# SCH_NightLightAnnunciator_2021-09-26.net
KiCad netlist of a schematic drawn in EasyEDA
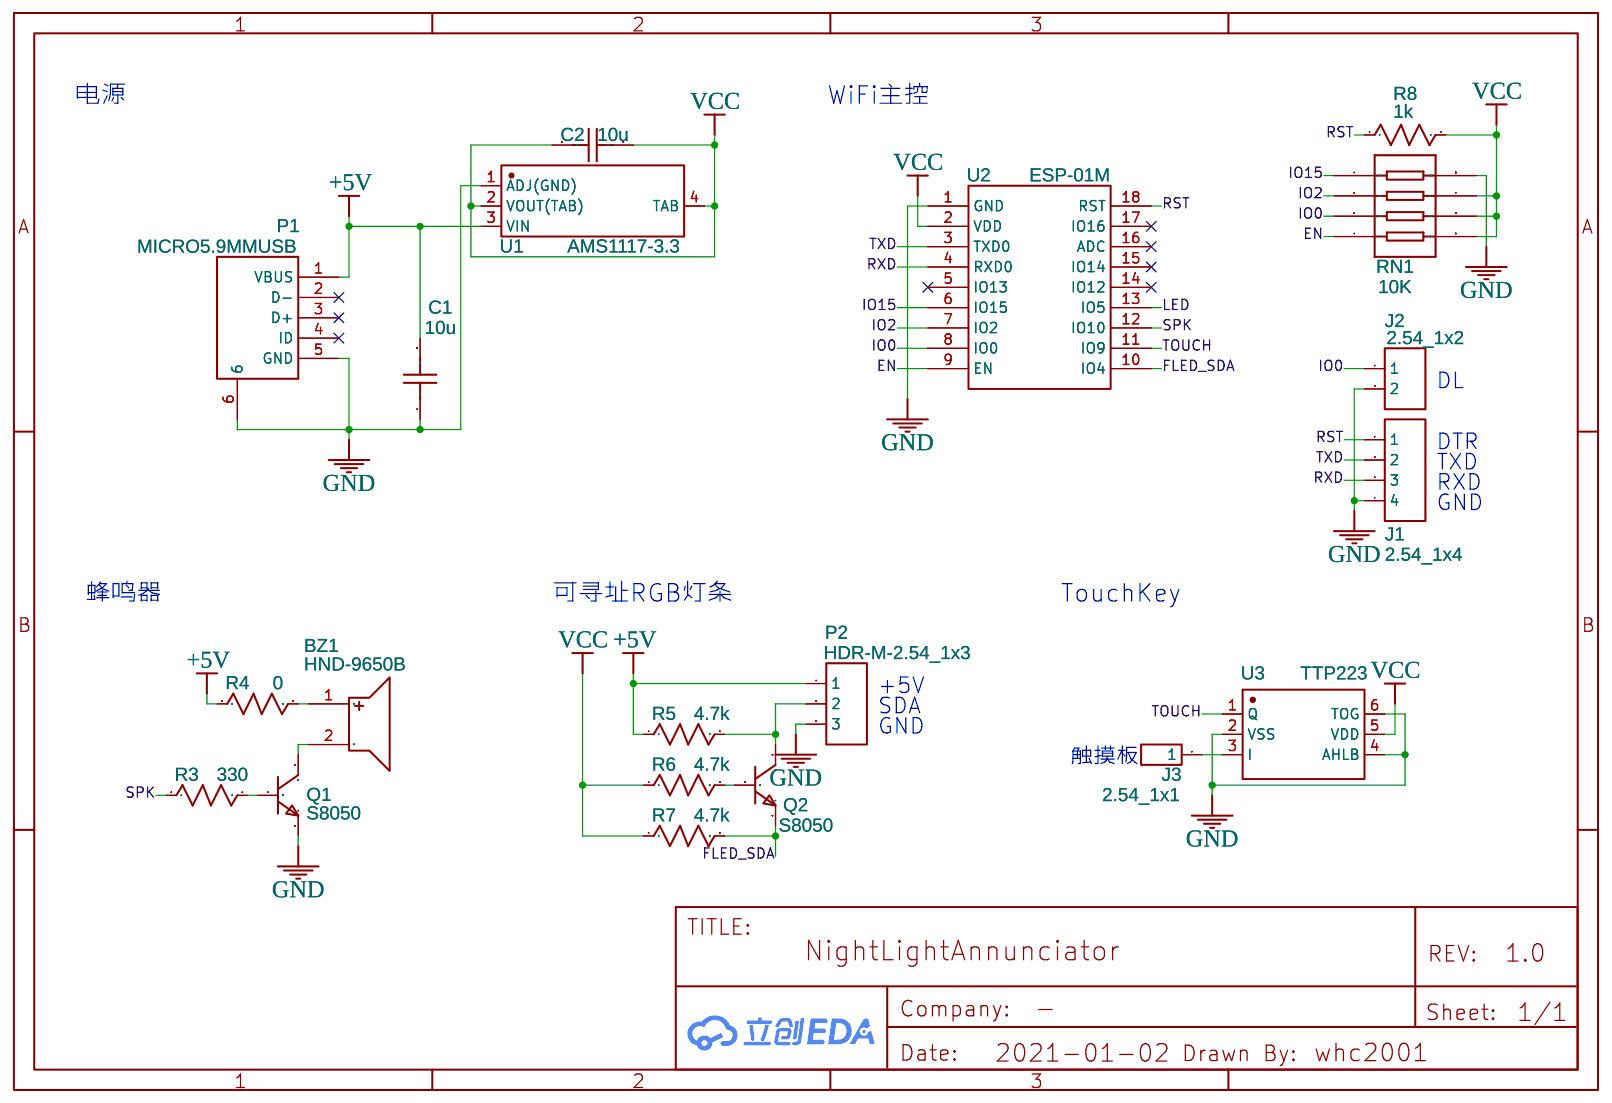
[diagram p0: schematic sheet]

(export (version "E")
  (design (tool "Eeschema 10.0.6"))
  (components
    (comp (ref "BZ1")
      (value "HND-9650B")
      (fields (field (name "BOM_Supplier Part") "C96127"))
      (libsource (lib "") (part "HND-9650B"))
    )
    (comp (ref "C1") (value "10u") (libsource (lib "") (part "C_0603_US")))
    (comp (ref "C2") (value "10u") (libsource (lib "") (part "C_0603_US_1")))
    (comp (ref "J1")
      (value "2.54_1x4")
      (fields (field (name "BOM_Supplier Part") "C124378"))
      (libsource (lib "") (part "HDR-M-2.54_1x4"))
    )
    (comp (ref "J2")
      (value "2.54_1x2")
      (fields (field (name "BOM_Supplier Part") "C124375"))
      (libsource (lib "") (part "HDR-M-2.54_1x2"))
    )
    (comp (ref "J3")
      (value "2.54_1x1")
      (fields (field (name "BOM_Supplier Part") "C81276"))
      (libsource (lib "") (part "HDR-M-2.54_1x1"))
    )
    (comp (ref "P1")
      (value "MICRO5.9MMUSB")
      (fields
        (field (name "BOM_Manufacturer Part") "MICRO5.9mmusb")
        (field (name "BOM_Supplier Part") "C393940")
      )
      (libsource (lib "") (part "MICRO5.9MMUSB"))
    )
    (comp (ref "P2")
      (value "HDR-M-2.54_1x3")
      (fields (field (name "BOM_Supplier Part") "C180248"))
      (libsource (lib "") (part "HDR-M-2.54_1x3"))
    )
    (comp (ref "Q1")
      (value "S8050")
      (fields (field (name "BOM_Manufacturer Part") "S8050-J3Y") (field (name "BOM_Supplier Part") "C364312"))
      (libsource (lib "") (part "S8050-J3Y"))
    )
    (comp (ref "Q2")
      (value "S8050")
      (fields (field (name "BOM_Manufacturer Part") "S8050-J3Y") (field (name "BOM_Supplier Part") "C364312"))
      (libsource (lib "") (part "S8050-J3Y"))
    )
    (comp (ref "R3") (value "330") (libsource (lib "") (part "R_0603_US")))
    (comp (ref "R4") (value "0") (libsource (lib "") (part "R_0603_US")))
    (comp (ref "R5") (value "4.7k") (libsource (lib "") (part "R_0603_US")))
    (comp (ref "R6") (value "4.7k") (libsource (lib "") (part "R_0603_US")))
    (comp (ref "R7") (value "4.7k") (libsource (lib "") (part "R_0603_US")))
    (comp (ref "R8") (value "1k") (libsource (lib "") (part "R_0603_US")))
    (comp (ref "RN1")
      (value "10K")
      (fields
        (field (name "BOM_Manufacturer Part") "CN1J4TTD103J")
        (field (name "BOM_Supplier Part") "C240723")
      )
      (libsource (lib "") (part "CN1J4TTD103J"))
    )
    (comp (ref "U1")
      (value "AMS1117-3.3")
      (fields (field (name "BOM_Supplier Part") "C347222"))
      (libsource (lib "") (part "AMS1117-3.3_C347222"))
    )
    (comp (ref "U2") (value "ESP-01M") (libsource (lib "") (part "ESP-01M")))
    (comp (ref "U3")
      (value "TTP223")
      (fields
        (field (name "BOM_Manufacturer Part") "TTP223E-HA6")
        (field (name "BOM_Supplier Part") "C129459")
      )
      (libsource (lib "") (part "TTP223E-HA6"))
    )
  )
  (nets
    (net (code "1") (name "+5V") (class "Default")
      (node (ref "C1") (pin "2") (pinfunction "2_2") (pintype "unspecified"))
      (node (ref "P1") (pin "1") (pinfunction "VBUS_1") (pintype "unspecified"))
      (node (ref "P2") (pin "1") (pinfunction "1_1") (pintype "input"))
      (node (ref "R4") (pin "1") (pinfunction "1_1") (pintype "unspecified"))
      (node (ref "R5") (pin "1") (pinfunction "1_1") (pintype "unspecified"))
      (node (ref "U1") (pin "3") (pinfunction "VIN_3") (pintype "unspecified"))
    )
    (net (code "2") (name "/EN") (class "Default")
      (node (ref "RN1") (pin "4") (pinfunction "4_4") (pintype "input"))
      (node (ref "U2") (pin "9") (pinfunction "EN_9") (pintype "unspecified"))
    )
    (net (code "3") (name "/FLED_SDA") (class "Default")
      (node (ref "Q2") (pin "2") (pinfunction "E_2") (pintype "unspecified"))
      (node (ref "R7") (pin "2") (pinfunction "2_2") (pintype "unspecified"))
      (node (ref "U2") (pin "10") (pinfunction "IO4_10") (pintype "unspecified"))
    )
    (net (code "4") (name "/IO0") (class "Default")
      (node (ref "J2") (pin "1") (pinfunction "1_1") (pintype "unspecified"))
      (node (ref "RN1") (pin "3") (pinfunction "3_3") (pintype "input"))
      (node (ref "U2") (pin "8") (pinfunction "IO0_8") (pintype "unspecified"))
    )
    (net (code "5") (name "/IO2") (class "Default")
      (node (ref "RN1") (pin "2") (pinfunction "2_2") (pintype "input"))
      (node (ref "U2") (pin "7") (pinfunction "IO2_7") (pintype "unspecified"))
    )
    (net (code "6") (name "/IO15") (class "Default")
      (node (ref "RN1") (pin "1") (pinfunction "1_1") (pintype "input"))
      (node (ref "U2") (pin "6") (pinfunction "IO15_6") (pintype "unspecified"))
    )
    (net (code "7") (name "/LED") (class "Default")
      (node (ref "U2") (pin "13") (pinfunction "IO5_13") (pintype "unspecified"))
    )
    (net (code "8") (name "/RST") (class "Default")
      (node (ref "J1") (pin "1") (pinfunction "1_1") (pintype "unspecified"))
      (node (ref "R8") (pin "1") (pinfunction "1_1") (pintype "unspecified"))
      (node (ref "U2") (pin "18") (pinfunction "RST_18") (pintype "unspecified"))
    )
    (net (code "9") (name "/RXD") (class "Default")
      (node (ref "J1") (pin "3") (pinfunction "3_3") (pintype "unspecified"))
      (node (ref "U2") (pin "4") (pinfunction "RXD0_4") (pintype "unspecified"))
    )
    (net (code "10") (name "/SPK") (class "Default")
      (node (ref "R3") (pin "1") (pinfunction "1_1") (pintype "unspecified"))
      (node (ref "U2") (pin "12") (pinfunction "IO10_12") (pintype "unspecified"))
    )
    (net (code "11") (name "/TOUCH") (class "Default")
      (node (ref "U2") (pin "11") (pinfunction "IO9_11") (pintype "unspecified"))
      (node (ref "U3") (pin "1") (pinfunction "Q_1") (pintype "unspecified"))
    )
    (net (code "12") (name "/TXD") (class "Default")
      (node (ref "J1") (pin "2") (pinfunction "2_2") (pintype "unspecified"))
      (node (ref "U2") (pin "3") (pinfunction "TXD0_3") (pintype "unspecified"))
    )
    (net (code "13") (name "GND") (class "Default")
      (node (ref "C1") (pin "1") (pinfunction "1_1") (pintype "unspecified"))
      (node (ref "J1") (pin "4") (pinfunction "4_4") (pintype "unspecified"))
      (node (ref "J2") (pin "2") (pinfunction "2_2") (pintype "unspecified"))
      (node (ref "P1") (pin "5") (pinfunction "GND_5") (pintype "unspecified"))
      (node (ref "P1") (pin "6") (pinfunction "6_6") (pintype "unspecified"))
      (node (ref "P2") (pin "3") (pinfunction "3_3") (pintype "input"))
      (node (ref "Q1") (pin "2") (pinfunction "E_2") (pintype "unspecified"))
      (node (ref "RN1") (pin "8") (pinfunction "8_8") (pintype "input"))
      (node (ref "U1") (pin "1") (pinfunction "ADJ(GND)_1") (pintype "unspecified"))
      (node (ref "U2") (pin "1") (pinfunction "GND_1") (pintype "unspecified"))
      (node (ref "U3") (pin "2") (pinfunction "VSS_2") (pintype "unspecified"))
      (node (ref "U3") (pin "4") (pinfunction "AHLB_4") (pintype "unspecified"))
      (node (ref "U3") (pin "6") (pinfunction "TOG_6") (pintype "unspecified"))
    )
    (net (code "14") (name "Net-(BZ1-Pad1)") (class "Default")
      (node (ref "BZ1") (pin "1") (pinfunction "1_1") (pintype "unspecified"))
      (node (ref "R4") (pin "2") (pinfunction "2_2") (pintype "unspecified"))
    )
    (net (code "15") (name "Net-(Q1-B)") (class "Default")
      (node (ref "Q1") (pin "1") (pinfunction "B_1") (pintype "unspecified"))
      (node (ref "R3") (pin "2") (pinfunction "2_2") (pintype "unspecified"))
    )
    (net (code "16") (name "Net-(Q1-C)") (class "Default")
      (node (ref "BZ1") (pin "2") (pinfunction "2_2") (pintype "unspecified"))
      (node (ref "Q1") (pin "3") (pinfunction "C_3") (pintype "unspecified"))
    )
    (net (code "17") (name "Net-(Q2-B)") (class "Default")
      (node (ref "Q2") (pin "1") (pinfunction "B_1") (pintype "unspecified"))
      (node (ref "R6") (pin "2") (pinfunction "2_2") (pintype "unspecified"))
    )
    (net (code "18") (name "Net-(Q2-C)") (class "Default")
      (node (ref "P2") (pin "2") (pinfunction "2_2") (pintype "input"))
      (node (ref "Q2") (pin "3") (pinfunction "C_3") (pintype "unspecified"))
      (node (ref "R5") (pin "2") (pinfunction "2_2") (pintype "unspecified"))
    )
    (net (code "19") (name "Net-(U3-I)") (class "Default")
      (node (ref "J3") (pin "1") (pinfunction "1_1") (pintype "input"))
      (node (ref "U3") (pin "3") (pinfunction "I_3") (pintype "unspecified"))
    )
    (net (code "20") (name "VCC") (class "Default")
      (node (ref "C2") (pin "1") (pinfunction "1_1") (pintype "unspecified"))
      (node (ref "C2") (pin "2") (pinfunction "2_2") (pintype "unspecified"))
      (node (ref "R6") (pin "1") (pinfunction "1_1") (pintype "unspecified"))
      (node (ref "R7") (pin "1") (pinfunction "1_1") (pintype "unspecified"))
      (node (ref "R8") (pin "2") (pinfunction "2_2") (pintype "unspecified"))
      (node (ref "RN1") (pin "5") (pinfunction "5_5") (pintype "input"))
      (node (ref "RN1") (pin "6") (pinfunction "6_6") (pintype "input"))
      (node (ref "RN1") (pin "7") (pinfunction "7_7") (pintype "input"))
      (node (ref "U1") (pin "2") (pinfunction "VOUT(TAB)_2") (pintype "unspecified"))
      (node (ref "U1") (pin "4") (pinfunction "TAB_4") (pintype "unspecified"))
      (node (ref "U2") (pin "2") (pinfunction "VDD_2") (pintype "unspecified"))
      (node (ref "U3") (pin "5") (pinfunction "VDD_5") (pintype "unspecified"))
    )
    (net (code "21") (name "unconnected-(P1-D+-Pad3)") (class "Default")
      (node (ref "P1") (pin "3") (pinfunction "D+_3") (pintype "unspecified+no_connect"))
    )
    (net (code "22") (name "unconnected-(P1-D--Pad2)") (class "Default")
      (node (ref "P1") (pin "2") (pinfunction "D-_2") (pintype "unspecified+no_connect"))
    )
    (net (code "23") (name "unconnected-(P1-ID-Pad4)") (class "Default")
      (node (ref "P1") (pin "4") (pinfunction "ID_4") (pintype "unspecified+no_connect"))
    )
    (net (code "24") (name "unconnected-(U2-ADC-Pad16)") (class "Default")
      (node (ref "U2") (pin "16") (pinfunction "ADC_16") (pintype "unspecified+no_connect"))
    )
    (net (code "25") (name "unconnected-(U2-IO12-Pad14)") (class "Default")
      (node (ref "U2") (pin "14") (pinfunction "IO12_14") (pintype "unspecified+no_connect"))
    )
    (net (code "26") (name "unconnected-(U2-IO13-Pad5)") (class "Default")
      (node (ref "U2") (pin "5") (pinfunction "IO13_5") (pintype "unspecified+no_connect"))
    )
    (net (code "27") (name "unconnected-(U2-IO14-Pad15)") (class "Default")
      (node (ref "U2") (pin "15") (pinfunction "IO14_15") (pintype "unspecified+no_connect"))
    )
    (net (code "28") (name "unconnected-(U2-IO16-Pad17)") (class "Default")
      (node (ref "U2") (pin "17") (pinfunction "IO16_17") (pintype "unspecified+no_connect"))
    )
  )
)
